# SMA-Q2_replacement_board.net
KiCad netlist of a schematic drawn in EAGLE
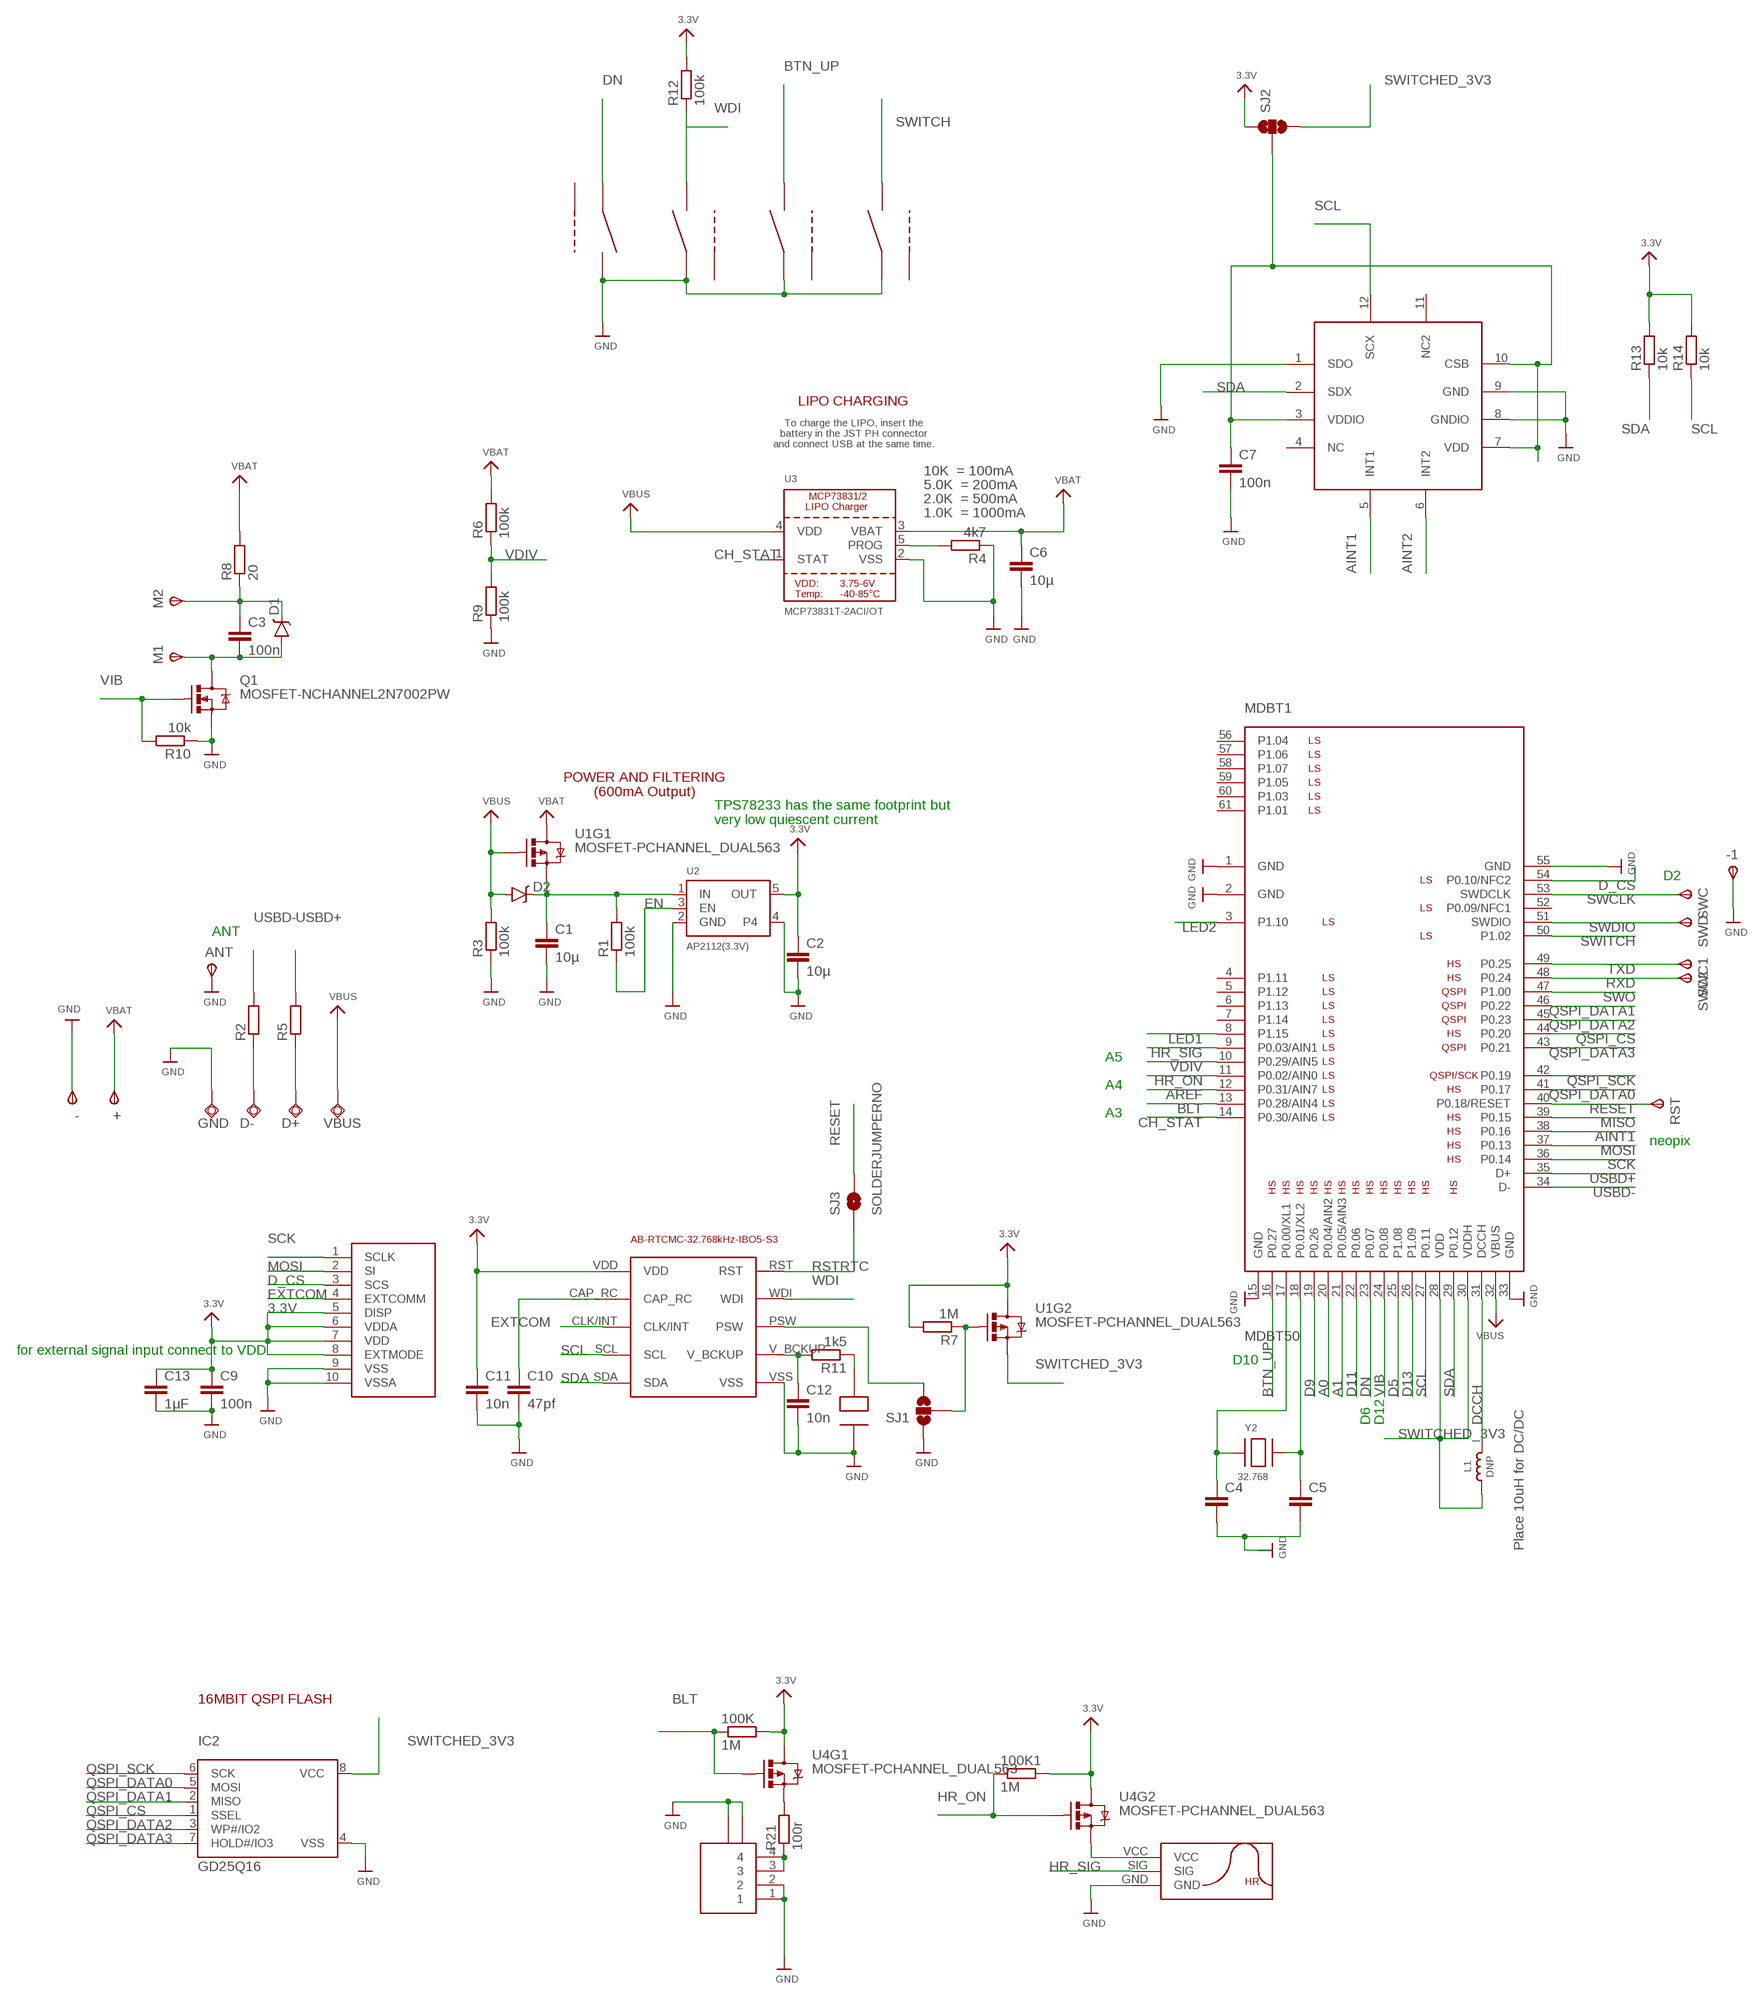
[diagram p0: schematic, sheet 1]

(export (version "E")
  (design (tool "Eeschema 10.0.6"))
  (components
    (comp (ref "+")
      (value "TPSTP09R")
      (footprint "eagle-import:TP09R")
      (libsource (lib "eagle-import") (part "TPSTP09R"))
    )
    (comp (ref "-")
      (value "TPSTP09R")
      (footprint "eagle-import:TP09R")
      (libsource (lib "eagle-import") (part "TPSTP09R"))
    )
    (comp (ref "-1")
      (value "TPSTP09R")
      (footprint "eagle-import:TP09R")
      (libsource (lib "eagle-import") (part "TPSTP09R"))
    )
    (comp (ref "100K")
      (value "1M")
      (footprint "eagle-import:R0402")
      (libsource (lib "eagle-import") (part "R-EU_R0402"))
    )
    (comp (ref "100K1")
      (value "1M")
      (footprint "eagle-import:R0402")
      (libsource (lib "eagle-import") (part "R-EU_R0402"))
    )
    (comp (ref "ANT")
      (value "TPSTP19SQ")
      (footprint "eagle-import:TP19SQ")
      (libsource (lib "eagle-import") (part "TPSTP19SQ"))
    )
    (comp (ref "C1")
      (value "10µ")
      (footprint "eagle-import:C0603")
      (libsource (lib "eagle-import") (part "C-EUC0603"))
    )
    (comp (ref "C2")
      (value "10µ")
      (footprint "eagle-import:C0603")
      (libsource (lib "eagle-import") (part "C-EUC0603"))
    )
    (comp (ref "C3")
      (value "100n")
      (footprint "eagle-import:C0402")
      (libsource (lib "eagle-import") (part "C-EUC0402"))
    )
    (comp (ref "C4")
      (value "C-EUC0402")
      (footprint "eagle-import:C0402")
      (libsource (lib "eagle-import") (part "C-EUC0402"))
    )
    (comp (ref "C5")
      (value "C-EUC0402")
      (footprint "eagle-import:C0402")
      (libsource (lib "eagle-import") (part "C-EUC0402"))
    )
    (comp (ref "C6")
      (value "10µ")
      (footprint "eagle-import:C0603")
      (libsource (lib "eagle-import") (part "C-EUC0603"))
    )
    (comp (ref "C7")
      (value "100n")
      (footprint "eagle-import:C0402")
      (libsource (lib "eagle-import") (part "C-EUC0402"))
    )
    (comp (ref "C9")
      (value "100n")
      (footprint "eagle-import:C0402")
      (libsource (lib "eagle-import") (part "C-EUC0402"))
    )
    (comp (ref "C10")
      (value "47pf")
      (footprint "eagle-import:C0402")
      (libsource (lib "eagle-import") (part "C-EUC0402"))
    )
    (comp (ref "C11")
      (value "10n")
      (footprint "eagle-import:C0402")
      (libsource (lib "eagle-import") (part "C-EUC0402"))
    )
    (comp (ref "C12")
      (value "10n")
      (footprint "eagle-import:C0402")
      (libsource (lib "eagle-import") (part "C-EUC0402"))
    )
    (comp (ref "C13")
      (value "1µF")
      (footprint "eagle-import:C0402")
      (libsource (lib "eagle-import") (part "C-EUC0402"))
    )
    (comp (ref "D+")
      (value "TPSQTP20R")
      (footprint "eagle-import:TP20R")
      (libsource (lib "eagle-import") (part "TPSQTP20R"))
    )
    (comp (ref "D-")
      (value "TPSQTP20R")
      (footprint "eagle-import:TP20R")
      (libsource (lib "eagle-import") (part "TPSQTP20R"))
    )
    (comp (ref "D1")
      (value "BAT20J")
      (footprint "eagle-import:SOD-323")
      (libsource (lib "eagle-import") (part "DIODE-SCHOTTKY-BAT20J"))
    )
    (comp (ref "D2")
      (value "BAT20J")
      (footprint "eagle-import:SOD-323")
      (libsource (lib "eagle-import") (part "DIODE-SCHOTTKY-BAT20J"))
    )
    (comp (ref "DWN")
      (value "LS12T2")
      (footprint "eagle-import:LS12T2")
      (libsource (lib "eagle-import") (part "LS12T2"))
    )
    (comp (ref "DWN1")
      (value "LS12T2")
      (footprint "eagle-import:LS12T2")
      (libsource (lib "eagle-import") (part "LS12T2"))
    )
    (comp (ref "DWN2")
      (value "LS12T2")
      (footprint "eagle-import:LS12T2")
      (libsource (lib "eagle-import") (part "LS12T2"))
    )
    (comp (ref "DWN3")
      (value "LS12T2")
      (footprint "eagle-import:LS12T2")
      (libsource (lib "eagle-import") (part "LS12T2"))
    )
    (comp (ref "GND")
      (value "TPSQTP20R")
      (footprint "eagle-import:TP20R")
      (libsource (lib "eagle-import") (part "TPSQTP20R"))
    )
    (comp (ref "IC2")
      (value "GD25Q16")
      (footprint "eagle-import:USON8")
      (libsource (lib "eagle-import") (part "SPIFLASH_8PINUX"))
    )
    (comp (ref "L1")
      (value "DNP")
      (footprint "eagle-import:_0805MP")
      (libsource (lib "eagle-import") (part "INDUCTOR_0805MP"))
    )
    (comp (ref "M1")
      (value "TPSTP09R")
      (footprint "eagle-import:TP09R")
      (libsource (lib "eagle-import") (part "TPSTP09R"))
    )
    (comp (ref "M2")
      (value "TPSTP09R")
      (footprint "eagle-import:TP09R")
      (libsource (lib "eagle-import") (part "TPSTP09R"))
    )
    (comp (ref "MDBT1")
      (value "MDBT50")
      (footprint "eagle-import:MDBT50")
      (libsource (lib "eagle-import") (part "MDBT50"))
    )
    (comp (ref "Q1")
      (value "MOSFET-NCHANNEL2N7002PW")
      (footprint "eagle-import:SOT323")
      (libsource (lib "eagle-import") (part "MOSFET-NCHANNEL2N7002PW"))
    )
    (comp (ref "R1")
      (value "100k")
      (footprint "eagle-import:R0402")
      (libsource (lib "eagle-import") (part "R-EU_R0402"))
    )
    (comp (ref "R2")
      (value "R-EU_R0402")
      (footprint "eagle-import:R0402")
      (libsource (lib "eagle-import") (part "R-EU_R0402"))
    )
    (comp (ref "R3")
      (value "100k")
      (footprint "eagle-import:R0402")
      (libsource (lib "eagle-import") (part "R-EU_R0402"))
    )
    (comp (ref "R4")
      (value "4k7")
      (footprint "eagle-import:R0402")
      (libsource (lib "eagle-import") (part "R-EU_R0402"))
    )
    (comp (ref "R5")
      (value "R-EU_R0402")
      (footprint "eagle-import:R0402")
      (libsource (lib "eagle-import") (part "R-EU_R0402"))
    )
    (comp (ref "R6")
      (value "100k")
      (footprint "eagle-import:R0402")
      (libsource (lib "eagle-import") (part "R-EU_R0402"))
    )
    (comp (ref "R7")
      (value "1M")
      (footprint "eagle-import:R0402")
      (libsource (lib "eagle-import") (part "R-EU_R0402"))
    )
    (comp (ref "R8")
      (value "20")
      (footprint "eagle-import:R0402")
      (libsource (lib "eagle-import") (part "R-EU_R0402"))
    )
    (comp (ref "R9")
      (value "100k")
      (footprint "eagle-import:R0402")
      (libsource (lib "eagle-import") (part "R-EU_R0402"))
    )
    (comp (ref "R10")
      (value "10k")
      (footprint "eagle-import:R0402")
      (libsource (lib "eagle-import") (part "R-EU_R0402"))
    )
    (comp (ref "R11")
      (value "1k5")
      (footprint "eagle-import:R0402")
      (libsource (lib "eagle-import") (part "R-EU_R0402"))
    )
    (comp (ref "R12")
      (value "100k")
      (footprint "eagle-import:R0402")
      (libsource (lib "eagle-import") (part "R-EU_R0402"))
    )
    (comp (ref "R13")
      (value "10k")
      (footprint "eagle-import:R0402")
      (libsource (lib "eagle-import") (part "R-EU_R0402"))
    )
    (comp (ref "R14")
      (value "10k")
      (footprint "eagle-import:R0402")
      (libsource (lib "eagle-import") (part "R-EU_R0402"))
    )
    (comp (ref "R21")
      (value "100r")
      (footprint "eagle-import:R0402")
      (libsource (lib "eagle-import") (part "R-EU_R0402"))
    )
    (comp (ref "RST")
      (value "TPSTP09R")
      (footprint "eagle-import:TP09R")
      (libsource (lib "eagle-import") (part "TPSTP09R"))
    )
    (comp (ref "SJ1")
      (value "SOLDERJUMPER_2WAYS")
      (footprint "eagle-import:SJ_3")
      (libsource (lib "eagle-import") (part "SOLDERJUMPER_2WAYS"))
    )
    (comp (ref "SJ2")
      (value "SOLDERJUMPER_2WAYS")
      (footprint "eagle-import:SJ_3")
      (libsource (lib "eagle-import") (part "SOLDERJUMPER_2WAYS"))
    )
    (comp (ref "SJ3")
      (value "SOLDERJUMPERNO")
      (footprint "eagle-import:SJ_2S-NO")
      (libsource (lib "eagle-import") (part "SOLDERJUMPERNO"))
    )
    (comp (ref "SWC")
      (value "TPSTP09R")
      (footprint "eagle-import:TP09R")
      (libsource (lib "eagle-import") (part "TPSTP09R"))
    )
    (comp (ref "SWC1")
      (value "TPSTP09R")
      (footprint "eagle-import:TP09R")
      (libsource (lib "eagle-import") (part "TPSTP09R"))
    )
    (comp (ref "SWC2")
      (value "TPSTP09R")
      (footprint "eagle-import:TP09R")
      (libsource (lib "eagle-import") (part "TPSTP09R"))
    )
    (comp (ref "SWD")
      (value "TPSTP09R")
      (footprint "eagle-import:TP09R")
      (libsource (lib "eagle-import") (part "TPSTP09R"))
    )
    (comp (ref "U$1")
      (value "AB-RTCMC-32.768KHZ-IBO5-S3")
      (footprint "eagle-import:AB-RTCMC-32.768KHZ-IBO5-S3")
      (libsource (lib "eagle-import") (part "AB-RTCMC-32.768KHZ-IBO5-S3"))
    )
    (comp (ref "U$2")
      (value "SHARP_MEM_DISP")
      (footprint "eagle-import:Y5BW")
      (libsource (lib "eagle-import") (part "SHARP_MEM_DISP"))
    )
    (comp (ref "U$6")
      (value "Y5B-4PIN")
      (footprint "eagle-import:Y5B-4PIN")
      (libsource (lib "eagle-import") (part "Y5B-4PIN"))
    )
    (comp (ref "U$7")
      (value "BMA400")
      (footprint "eagle-import:BMA400")
      (libsource (lib "eagle-import") (part "BMA400"))
    )
    (comp (ref "U$15")
      (value "CPH3225A")
      (footprint "eagle-import:CPH3225A")
      (libsource (lib "eagle-import") (part "CPH3225A"))
    )
    (comp (ref "U$45")
      (value "HR_PADS")
      (footprint "eagle-import:HR_PADS")
      (libsource (lib "eagle-import") (part "HR_PADS"))
    )
    (comp (ref "U1")
      (value "MOSFET-PCHANNEL_DUAL563")
      (footprint "eagle-import:SOT563")
      (libsource (lib "eagle-import") (part "MOSFET-PCHANNEL_DUAL563"))
    )
    (comp (ref "U2")
      (value "AP2112(3.3V)")
      (footprint "eagle-import:SOT23-5")
      (libsource (lib "eagle-import") (part "VREG_SOT23-5"))
    )
    (comp (ref "U3")
      (value "MCP73831T-2ACI/OT")
      (footprint "eagle-import:SOT23-5")
      (libsource (lib "eagle-import") (part "MCP73831/2"))
    )
    (comp (ref "U4")
      (value "MOSFET-PCHANNEL_DUAL563")
      (footprint "eagle-import:SOT563")
      (libsource (lib "eagle-import") (part "MOSFET-PCHANNEL_DUAL563"))
    )
    (comp (ref "VBUS")
      (value "TPSQTP20R")
      (footprint "eagle-import:TP20R")
      (libsource (lib "eagle-import") (part "TPSQTP20R"))
    )
    (comp (ref "Y2")
      (value "32.768")
      (footprint "eagle-import:XTAL3215")
      (libsource (lib "eagle-import") (part "XTAL-3.2X1.5"))
    )
  )
  (nets
    (net (code "1") (name "/A0") (class "Default")
      (node (ref "MDBT1") (pin "20") (pinfunction "P0.04/AIN2_20") (pintype "bidirectional"))
    )
    (net (code "2") (name "/A1") (class "Default")
      (node (ref "MDBT1") (pin "21") (pinfunction "P0.05/AIN3_21") (pintype "bidirectional"))
    )
    (net (code "3") (name "/AINT1") (class "Default")
      (node (ref "MDBT1") (pin "38") (pinfunction "P0.16_38") (pintype "bidirectional"))
      (node (ref "U$7") (pin "5") (pinfunction "INT1_5") (pintype "bidirectional"))
    )
    (net (code "4") (name "/AINT2") (class "Default")
      (node (ref "U$7") (pin "6") (pinfunction "INT2_6") (pintype "bidirectional"))
    )
    (net (code "5") (name "/AREF") (class "Default")
      (node (ref "MDBT1") (pin "12") (pinfunction "P0.31/AIN7_12") (pintype "bidirectional"))
    )
    (net (code "6") (name "/BLT") (class "Default")
      (node (ref "100K") (pin "1") (pinfunction "1_1") (pintype "passive"))
      (node (ref "MDBT1") (pin "13") (pinfunction "P0.28/AIN4_13") (pintype "bidirectional"))
      (node (ref "U4") (pin "G1") (pinfunction "G_G1") (pintype "passive"))
    )
    (net (code "7") (name "/BTN_UP") (class "Default")
      (node (ref "DWN2") (pin "1") (pinfunction "1_1") (pintype "bidirectional"))
      (node (ref "MDBT1") (pin "16") (pinfunction "P0.27_16") (pintype "bidirectional"))
    )
    (net (code "8") (name "/CH_STAT") (class "Default")
      (node (ref "MDBT1") (pin "14") (pinfunction "P0.30/AIN6_14") (pintype "bidirectional"))
      (node (ref "U3") (pin "1") (pinfunction "STAT_1") (pintype "output"))
    )
    (net (code "9") (name "/D5") (class "Default")
      (node (ref "MDBT1") (pin "25") (pinfunction "P1.08_25") (pintype "bidirectional"))
    )
    (net (code "10") (name "/D9") (class "Default")
      (node (ref "MDBT1") (pin "19") (pinfunction "P0.26_19") (pintype "bidirectional"))
    )
    (net (code "11") (name "/D11") (class "Default")
      (node (ref "MDBT1") (pin "22") (pinfunction "P0.06_22") (pintype "bidirectional"))
    )
    (net (code "12") (name "/D13") (class "Default")
      (node (ref "MDBT1") (pin "26") (pinfunction "P1.09_26") (pintype "bidirectional"))
    )
    (net (code "13") (name "/DCCH") (class "Default")
      (node (ref "L1") (pin "2") (pinfunction "2_2") (pintype "passive"))
      (node (ref "MDBT1") (pin "31") (pinfunction "DCCH_31") (pintype "bidirectional"))
    )
    (net (code "14") (name "/DN") (class "Default")
      (node (ref "DWN") (pin "2") (pinfunction "2_2") (pintype "bidirectional"))
      (node (ref "MDBT1") (pin "23") (pinfunction "P0.07_23") (pintype "bidirectional"))
    )
    (net (code "15") (name "/D_CS") (class "Default")
      (node (ref "MDBT1") (pin "54") (pinfunction "P0.10/NFC2_54") (pintype "bidirectional"))
      (node (ref "U$2") (pin "3") (pinfunction "SCS_3") (pintype "bidirectional"))
    )
    (net (code "16") (name "/EN") (class "Default")
      (node (ref "R1") (pin "1") (pinfunction "1_1") (pintype "passive"))
      (node (ref "U2") (pin "3") (pinfunction "EN_3") (pintype "input"))
    )
    (net (code "17") (name "/EXTCOM") (class "Default")
      (node (ref "U$1") (pin "CLK/INT") (pinfunction "CLK/INT_CLK/INT") (pintype "bidirectional"))
      (node (ref "U$2") (pin "4") (pinfunction "EXTCOMM_4") (pintype "bidirectional"))
    )
    (net (code "18") (name "/HR_ON") (class "Default")
      (node (ref "100K1") (pin "1") (pinfunction "1_1") (pintype "passive"))
      (node (ref "MDBT1") (pin "11") (pinfunction "P0.02/AIN0_11") (pintype "bidirectional"))
      (node (ref "U4") (pin "G2") (pinfunction "G_G2") (pintype "passive"))
    )
    (net (code "19") (name "/HR_SIG") (class "Default")
      (node (ref "MDBT1") (pin "9") (pinfunction "P0.03/AIN1_9") (pintype "bidirectional"))
      (node (ref "U$45") (pin "SIG") (pinfunction "SIG_SIG") (pintype "bidirectional"))
    )
    (net (code "20") (name "/LED1") (class "Default")
      (node (ref "MDBT1") (pin "8") (pinfunction "P1.15_8") (pintype "bidirectional"))
    )
    (net (code "21") (name "/LED2") (class "Default")
      (node (ref "MDBT1") (pin "3") (pinfunction "P1.10_3") (pintype "bidirectional"))
    )
    (net (code "22") (name "/MISO") (class "Default")
      (node (ref "MDBT1") (pin "39") (pinfunction "P0.15_39") (pintype "bidirectional"))
    )
    (net (code "23") (name "/MOSI") (class "Default")
      (node (ref "MDBT1") (pin "37") (pinfunction "P0.13_37") (pintype "bidirectional"))
      (node (ref "U$2") (pin "2") (pinfunction "SI_2") (pintype "bidirectional"))
    )
    (net (code "24") (name "/QSPI_CS") (class "Default")
      (node (ref "IC2") (pin "1") (pinfunction "SSEL_1") (pintype "bidirectional"))
      (node (ref "MDBT1") (pin "44") (pinfunction "P0.20_44") (pintype "bidirectional"))
    )
    (net (code "25") (name "/QSPI_DATA0") (class "Default")
      (node (ref "IC2") (pin "5") (pinfunction "MOSI_5") (pintype "bidirectional"))
      (node (ref "MDBT1") (pin "41") (pinfunction "P0.17_41") (pintype "bidirectional"))
    )
    (net (code "26") (name "/QSPI_DATA1") (class "Default")
      (node (ref "IC2") (pin "2") (pinfunction "MISO_2") (pintype "bidirectional"))
      (node (ref "MDBT1") (pin "46") (pinfunction "P0.22_46") (pintype "bidirectional"))
    )
    (net (code "27") (name "/QSPI_DATA2") (class "Default")
      (node (ref "IC2") (pin "3") (pinfunction "WP#/IO2_3") (pintype "bidirectional"))
      (node (ref "MDBT1") (pin "45") (pinfunction "P0.23_45") (pintype "bidirectional"))
    )
    (net (code "28") (name "/QSPI_DATA3") (class "Default")
      (node (ref "IC2") (pin "7") (pinfunction "HOLD#/IO3_7") (pintype "bidirectional"))
      (node (ref "MDBT1") (pin "43") (pinfunction "P0.21_43") (pintype "bidirectional"))
    )
    (net (code "29") (name "/QSPI_SCK") (class "Default")
      (node (ref "IC2") (pin "6") (pinfunction "SCK_6") (pintype "bidirectional"))
      (node (ref "MDBT1") (pin "42") (pinfunction "P0.19_42") (pintype "bidirectional"))
    )
    (net (code "30") (name "/RESET") (class "Default")
      (node (ref "MDBT1") (pin "40") (pinfunction "P0.18/RESET_40") (pintype "bidirectional"))
      (node (ref "RST") (pin "TP") (pinfunction "PP_TP") (pintype "input"))
      (node (ref "SJ3") (pin "2") (pinfunction "2_2") (pintype "passive"))
    )
    (net (code "31") (name "/RSTRTC") (class "Default")
      (node (ref "SJ3") (pin "1") (pinfunction "1_1") (pintype "passive"))
      (node (ref "U$1") (pin "RST") (pinfunction "RST_RST") (pintype "bidirectional"))
    )
    (net (code "32") (name "/RXD") (class "Default")
      (node (ref "MDBT1") (pin "48") (pinfunction "P0.24_48") (pintype "bidirectional"))
      (node (ref "SWC2") (pin "TP") (pinfunction "PP_TP") (pintype "input"))
    )
    (net (code "33") (name "/SCK") (class "Default")
      (node (ref "MDBT1") (pin "36") (pinfunction "P0.14_36") (pintype "bidirectional"))
      (node (ref "U$2") (pin "1") (pinfunction "SCLK_1") (pintype "bidirectional"))
    )
    (net (code "34") (name "/SCL") (class "Default")
      (node (ref "MDBT1") (pin "27") (pinfunction "P0.11_27") (pintype "bidirectional"))
      (node (ref "R14") (pin "1") (pinfunction "1_1") (pintype "passive"))
      (node (ref "U$1") (pin "SCL") (pinfunction "SCL_SCL") (pintype "bidirectional"))
      (node (ref "U$7") (pin "12") (pinfunction "SCX_12") (pintype "bidirectional"))
    )
    (net (code "35") (name "/SDA") (class "Default")
      (node (ref "MDBT1") (pin "29") (pinfunction "P0.12_29") (pintype "bidirectional"))
      (node (ref "R13") (pin "1") (pinfunction "1_1") (pintype "passive"))
      (node (ref "U$1") (pin "SDA") (pinfunction "SDA_SDA") (pintype "bidirectional"))
      (node (ref "U$7") (pin "2") (pinfunction "SDX_2") (pintype "bidirectional"))
    )
    (net (code "36") (name "/SWCLK") (class "Default")
      (node (ref "MDBT1") (pin "53") (pinfunction "SWDCLK_53") (pintype "bidirectional"))
      (node (ref "SWC") (pin "TP") (pinfunction "PP_TP") (pintype "input"))
    )
    (net (code "37") (name "/SWDIO") (class "Default")
      (node (ref "MDBT1") (pin "51") (pinfunction "SWDIO_51") (pintype "bidirectional"))
      (node (ref "SWD") (pin "TP") (pinfunction "PP_TP") (pintype "input"))
    )
    (net (code "38") (name "/SWITCH") (class "Default")
      (node (ref "DWN3") (pin "1") (pinfunction "1_1") (pintype "bidirectional"))
      (node (ref "MDBT1") (pin "50") (pinfunction "P1.02_50") (pintype "bidirectional"))
    )
    (net (code "39") (name "/SWITCHED_3V3") (class "Default")
      (node (ref "IC2") (pin "8") (pinfunction "VCC_8") (pintype "bidirectional"))
      (node (ref "L1") (pin "1") (pinfunction "1_1") (pintype "passive"))
      (node (ref "MDBT1") (pin "28") (pinfunction "VDD_28") (pintype "bidirectional"))
      (node (ref "MDBT1") (pin "30") (pinfunction "VDDH_30") (pintype "bidirectional"))
      (node (ref "SJ2") (pin "3") (pinfunction "3_3") (pintype "passive"))
      (node (ref "U1") (pin "S2") (pinfunction "S_S2") (pintype "passive"))
    )
    (net (code "40") (name "/SWO") (class "Default")
      (node (ref "MDBT1") (pin "47") (pinfunction "P1.00_47") (pintype "bidirectional"))
    )
    (net (code "41") (name "/TXD") (class "Default")
      (node (ref "MDBT1") (pin "49") (pinfunction "P0.25_49") (pintype "bidirectional"))
      (node (ref "SWC1") (pin "TP") (pinfunction "PP_TP") (pintype "input"))
    )
    (net (code "42") (name "/USBD+") (class "Default")
      (node (ref "MDBT1") (pin "35") (pinfunction "D+_35") (pintype "bidirectional"))
      (node (ref "R5") (pin "2") (pinfunction "2_2") (pintype "passive"))
    )
    (net (code "43") (name "/USBD-") (class "Default")
      (node (ref "MDBT1") (pin "34") (pinfunction "D-_34") (pintype "bidirectional"))
      (node (ref "R2") (pin "2") (pinfunction "2_2") (pintype "passive"))
    )
    (net (code "44") (name "/VDIV") (class "Default")
      (node (ref "MDBT1") (pin "10") (pinfunction "P0.29/AIN5_10") (pintype "bidirectional"))
      (node (ref "R6") (pin "1") (pinfunction "1_1") (pintype "passive"))
      (node (ref "R9") (pin "2") (pinfunction "2_2") (pintype "passive"))
    )
    (net (code "45") (name "/VIB") (class "Default")
      (node (ref "MDBT1") (pin "24") (pinfunction "P0.08_24") (pintype "bidirectional"))
      (node (ref "Q1") (pin "1") (pinfunction "G_1") (pintype "passive"))
      (node (ref "R10") (pin "2") (pinfunction "2_2") (pintype "passive"))
    )
    (net (code "46") (name "/WDI") (class "Default")
      (node (ref "DWN1") (pin "1") (pinfunction "1_1") (pintype "bidirectional"))
      (node (ref "R12") (pin "1") (pinfunction "1_1") (pintype "passive"))
      (node (ref "U$1") (pin "WDI") (pinfunction "WDI_WDI") (pintype "bidirectional"))
    )
    (net (code "47") (name "3.3V") (class "Default")
      (node (ref "100K") (pin "2") (pinfunction "2_2") (pintype "passive"))
      (node (ref "100K1") (pin "2") (pinfunction "2_2") (pintype "passive"))
      (node (ref "C11") (pin "1") (pinfunction "1_1") (pintype "passive"))
      (node (ref "C13") (pin "1") (pinfunction "1_1") (pintype "passive"))
      (node (ref "C2") (pin "1") (pinfunction "1_1") (pintype "passive"))
      (node (ref "C9") (pin "1") (pinfunction "1_1") (pintype "passive"))
      (node (ref "R12") (pin "2") (pinfunction "2_2") (pintype "passive"))
      (node (ref "R13") (pin "2") (pinfunction "2_2") (pintype "passive"))
      (node (ref "R14") (pin "2") (pinfunction "2_2") (pintype "passive"))
      (node (ref "R7") (pin "2") (pinfunction "2_2") (pintype "passive"))
      (node (ref "SJ2") (pin "1") (pinfunction "1_1") (pintype "passive"))
      (node (ref "U$1") (pin "VDD") (pinfunction "VDD_VDD") (pintype "bidirectional"))
      (node (ref "U$2") (pin "5") (pinfunction "DISP_5") (pintype "bidirectional"))
      (node (ref "U$2") (pin "6") (pinfunction "VDDA_6") (pintype "bidirectional"))
      (node (ref "U$2") (pin "7") (pinfunction "VDD_7") (pintype "bidirectional"))
      (node (ref "U$2") (pin "8") (pinfunction "EXTMODE_8") (pintype "bidirectional"))
      (node (ref "U1") (pin "D2") (pinfunction "D_D2") (pintype "passive"))
      (node (ref "U2") (pin "5") (pinfunction "OUT_5") (pintype "power_in"))
      (node (ref "U4") (pin "D1") (pinfunction "D_D1") (pintype "passive"))
      (node (ref "U4") (pin "D2") (pinfunction "D_D2") (pintype "passive"))
    )
    (net (code "48") (name "GND") (class "Default")
      (node (ref "-") (pin "TP") (pinfunction "PP_TP") (pintype "input"))
      (node (ref "-1") (pin "TP") (pinfunction "PP_TP") (pintype "input"))
      (node (ref "ANT") (pin "TP") (pinfunction "PP_TP") (pintype "input"))
      (node (ref "C1") (pin "2") (pinfunction "2_2") (pintype "passive"))
      (node (ref "C10") (pin "2") (pinfunction "2_2") (pintype "passive"))
      (node (ref "C11") (pin "2") (pinfunction "2_2") (pintype "passive"))
      (node (ref "C12") (pin "2") (pinfunction "2_2") (pintype "passive"))
      (node (ref "C13") (pin "2") (pinfunction "2_2") (pintype "passive"))
      (node (ref "C2") (pin "2") (pinfunction "2_2") (pintype "passive"))
      (node (ref "C4") (pin "2") (pinfunction "2_2") (pintype "passive"))
      (node (ref "C5") (pin "2") (pinfunction "2_2") (pintype "passive"))
      (node (ref "C6") (pin "2") (pinfunction "2_2") (pintype "passive"))
      (node (ref "C7") (pin "2") (pinfunction "2_2") (pintype "passive"))
      (node (ref "C9") (pin "2") (pinfunction "2_2") (pintype "passive"))
      (node (ref "DWN") (pin "1") (pinfunction "1_1") (pintype "bidirectional"))
      (node (ref "DWN1") (pin "2") (pinfunction "2_2") (pintype "bidirectional"))
      (node (ref "DWN2") (pin "2") (pinfunction "2_2") (pintype "bidirectional"))
      (node (ref "DWN3") (pin "2") (pinfunction "2_2") (pintype "bidirectional"))
      (node (ref "GND") (pin "TP") (pinfunction "TP_TP") (pintype "input"))
      (node (ref "IC2") (pin "4") (pinfunction "VSS_4") (pintype "bidirectional"))
      (node (ref "MDBT1") (pin "1") (pinfunction "GND_1") (pintype "bidirectional"))
      (node (ref "MDBT1") (pin "15") (pinfunction "GND_15") (pintype "bidirectional"))
      (node (ref "MDBT1") (pin "2") (pinfunction "GND_2") (pintype "bidirectional"))
      (node (ref "MDBT1") (pin "33") (pinfunction "GND_33") (pintype "bidirectional"))
      (node (ref "MDBT1") (pin "55") (pinfunction "GND_55") (pintype "bidirectional"))
      (node (ref "Q1") (pin "2") (pinfunction "S_2") (pintype "passive"))
      (node (ref "R10") (pin "1") (pinfunction "1_1") (pintype "passive"))
      (node (ref "R3") (pin "1") (pinfunction "1_1") (pintype "passive"))
      (node (ref "R4") (pin "1") (pinfunction "1_1") (pintype "passive"))
      (node (ref "R9") (pin "1") (pinfunction "1_1") (pintype "passive"))
      (node (ref "SJ1") (pin "1") (pinfunction "1_1") (pintype "passive"))
      (node (ref "U$1") (pin "VSS") (pinfunction "VSS_VSS") (pintype "bidirectional"))
      (node (ref "U$15") (pin "-") (pinfunction "-_-") (pintype "bidirectional"))
      (node (ref "U$2") (pin "10") (pinfunction "VSSA_10") (pintype "bidirectional"))
      (node (ref "U$2") (pin "9") (pinfunction "VSS_9") (pintype "bidirectional"))
      (node (ref "U$45") (pin "GND") (pinfunction "GND_GND") (pintype "bidirectional"))
      (node (ref "U$6") (pin "1") (pinfunction "1_1") (pintype "bidirectional"))
      (node (ref "U$6") (pin "2") (pinfunction "2_2") (pintype "bidirectional"))
      (node (ref "U$6") (pin "H1") (pinfunction "P$5_H1") (pintype "bidirectional"))
      (node (ref "U$6") (pin "H2") (pinfunction "P$6_H2") (pintype "bidirectional"))
      (node (ref "U$7") (pin "1") (pinfunction "SDO_1") (pintype "bidirectional"))
      (node (ref "U$7") (pin "8") (pinfunction "GNDIO_8") (pintype "bidirectional"))
      (node (ref "U$7") (pin "9") (pinfunction "GND_9") (pintype "bidirectional"))
      (node (ref "U2") (pin "2") (pinfunction "GND_2") (pintype "power_in"))
      (node (ref "U2") (pin "4") (pinfunction "P4_4") (pintype "bidirectional"))
      (node (ref "U3") (pin "2") (pinfunction "VSS_2") (pintype "power_in"))
    )
    (net (code "49") (name "Net-(C10-Pad1)") (class "Default")
      (node (ref "C10") (pin "1") (pinfunction "1_1") (pintype "passive"))
      (node (ref "U$1") (pin "CAP_RC") (pinfunction "CAP_RC_CAP_RC") (pintype "bidirectional"))
    )
    (net (code "50") (name "Net-(C12-Pad1)") (class "Default")
      (node (ref "C12") (pin "1") (pinfunction "1_1") (pintype "passive"))
      (node (ref "R11") (pin "2") (pinfunction "2_2") (pintype "passive"))
      (node (ref "U$1") (pin "V_BCKUP") (pinfunction "V_BCKUP_V_BCKUP") (pintype "bidirectional"))
    )
    (net (code "51") (name "Net-(D+-PadTP)") (class "Default")
      (node (ref "D+") (pin "TP") (pinfunction "TP_TP") (pintype "input"))
      (node (ref "R5") (pin "1") (pinfunction "1_1") (pintype "passive"))
    )
    (net (code "52") (name "Net-(D--PadTP)") (class "Default")
      (node (ref "D-") (pin "TP") (pinfunction "TP_TP") (pintype "input"))
      (node (ref "R2") (pin "1") (pinfunction "1_1") (pintype "passive"))
    )
    (net (code "53") (name "Net-(M1-PP)") (class "Default")
      (node (ref "C3") (pin "2") (pinfunction "2_2") (pintype "passive"))
      (node (ref "D1") (pin "A") (pinfunction "A_A") (pintype "passive"))
      (node (ref "M1") (pin "TP") (pinfunction "PP_TP") (pintype "input"))
      (node (ref "Q1") (pin "3") (pinfunction "D_3") (pintype "passive"))
    )
    (net (code "54") (name "Net-(M2-PP)") (class "Default")
      (node (ref "C3") (pin "1") (pinfunction "1_1") (pintype "passive"))
      (node (ref "D1") (pin "C") (pinfunction "C_C") (pintype "passive"))
      (node (ref "M2") (pin "TP") (pinfunction "PP_TP") (pintype "input"))
      (node (ref "R8") (pin "1") (pinfunction "1_1") (pintype "passive"))
    )
    (net (code "55") (name "Net-(MDBT1-P0.00{slash}XL1)") (class "Default")
      (node (ref "C4") (pin "1") (pinfunction "1_1") (pintype "passive"))
      (node (ref "MDBT1") (pin "17") (pinfunction "P0.00/XL1_17") (pintype "bidirectional"))
      (node (ref "Y2") (pin "P$1") (pinfunction "P$1_P$1") (pintype "bidirectional"))
    )
    (net (code "56") (name "Net-(MDBT1-P0.01{slash}XL2)") (class "Default")
      (node (ref "C5") (pin "1") (pinfunction "1_1") (pintype "passive"))
      (node (ref "MDBT1") (pin "18") (pinfunction "P0.01/XL2_18") (pintype "bidirectional"))
      (node (ref "Y2") (pin "P$2") (pinfunction "P$2_P$2") (pintype "bidirectional"))
    )
    (net (code "57") (name "Net-(R11-Pad1)") (class "Default")
      (node (ref "R11") (pin "1") (pinfunction "1_1") (pintype "passive"))
      (node (ref "U$15") (pin "+") (pinfunction "+_+") (pintype "bidirectional"))
    )
    (net (code "58") (name "Net-(R21-Pad1)") (class "Default")
      (node (ref "R21") (pin "1") (pinfunction "1_1") (pintype "passive"))
      (node (ref "U$6") (pin "3") (pinfunction "3_3") (pintype "bidirectional"))
      (node (ref "U$6") (pin "4") (pinfunction "4_4") (pintype "bidirectional"))
    )
    (net (code "59") (name "Net-(SJ1-Pad3)") (class "Default")
      (node (ref "SJ1") (pin "3") (pinfunction "3_3") (pintype "passive"))
      (node (ref "U$1") (pin "PSW") (pinfunction "PSW_PSW") (pintype "bidirectional"))
    )
    (net (code "60") (name "Net-(U$7-CSB)") (class "Default")
      (node (ref "C7") (pin "1") (pinfunction "1_1") (pintype "passive"))
      (node (ref "SJ2") (pin "2") (pinfunction "2_2") (pintype "passive"))
      (node (ref "U$7") (pin "10") (pinfunction "CSB_10") (pintype "bidirectional"))
      (node (ref "U$7") (pin "3") (pinfunction "VDDIO_3") (pintype "bidirectional"))
      (node (ref "U$7") (pin "7") (pinfunction "VDD_7") (pintype "bidirectional"))
    )
    (net (code "61") (name "Net-(U1A-S)") (class "Default")
      (node (ref "C1") (pin "1") (pinfunction "1_1") (pintype "passive"))
      (node (ref "D2") (pin "C") (pinfunction "C_C") (pintype "passive"))
      (node (ref "R1") (pin "2") (pinfunction "2_2") (pintype "passive"))
      (node (ref "U1") (pin "S1") (pinfunction "S_S1") (pintype "passive"))
      (node (ref "U2") (pin "1") (pinfunction "IN_1") (pintype "power_in"))
    )
    (net (code "62") (name "Net-(U1B-G)") (class "Default")
      (node (ref "R7") (pin "1") (pinfunction "1_1") (pintype "passive"))
      (node (ref "SJ1") (pin "2") (pinfunction "2_2") (pintype "passive"))
      (node (ref "U1") (pin "G2") (pinfunction "G_G2") (pintype "passive"))
    )
    (net (code "63") (name "Net-(U3-PROG)") (class "Default")
      (node (ref "R4") (pin "2") (pinfunction "2_2") (pintype "passive"))
      (node (ref "U3") (pin "5") (pinfunction "PROG_5") (pintype "input"))
    )
    (net (code "64") (name "Net-(U4A-S)") (class "Default")
      (node (ref "R21") (pin "2") (pinfunction "2_2") (pintype "passive"))
      (node (ref "U4") (pin "S1") (pinfunction "S_S1") (pintype "passive"))
    )
    (net (code "65") (name "Net-(U4B-S)") (class "Default")
      (node (ref "U$45") (pin "VCC") (pinfunction "VCC_VCC") (pintype "bidirectional"))
      (node (ref "U4") (pin "S2") (pinfunction "S_S2") (pintype "passive"))
    )
    (net (code "66") (name "VBAT") (class "Default")
      (node (ref "+") (pin "TP") (pinfunction "PP_TP") (pintype "input"))
      (node (ref "C6") (pin "1") (pinfunction "1_1") (pintype "passive"))
      (node (ref "R6") (pin "2") (pinfunction "2_2") (pintype "passive"))
      (node (ref "R8") (pin "2") (pinfunction "2_2") (pintype "passive"))
      (node (ref "U1") (pin "D1") (pinfunction "D_D1") (pintype "passive"))
      (node (ref "U3") (pin "3") (pinfunction "VBAT_3") (pintype "power_in"))
    )
    (net (code "67") (name "VBUS") (class "Default")
      (node (ref "D2") (pin "A") (pinfunction "A_A") (pintype "passive"))
      (node (ref "MDBT1") (pin "32") (pinfunction "VBUS_32") (pintype "bidirectional"))
      (node (ref "R3") (pin "2") (pinfunction "2_2") (pintype "passive"))
      (node (ref "U1") (pin "G1") (pinfunction "G_G1") (pintype "passive"))
      (node (ref "U3") (pin "4") (pinfunction "VDD_4") (pintype "power_in"))
      (node (ref "VBUS") (pin "TP") (pinfunction "TP_TP") (pintype "input"))
    )
    (net (code "68") (name "unconnected-(DWN-FRM-PadFRAME)") (class "Default")
      (node (ref "DWN") (pin "FRAME") (pinfunction "FRM_FRAME") (pintype "bidirectional"))
    )
    (net (code "69") (name "unconnected-(DWN1-FRM-PadFRAME)") (class "Default")
      (node (ref "DWN1") (pin "FRAME") (pinfunction "FRM_FRAME") (pintype "bidirectional"))
    )
    (net (code "70") (name "unconnected-(DWN2-FRM-PadFRAME)") (class "Default")
      (node (ref "DWN2") (pin "FRAME") (pinfunction "FRM_FRAME") (pintype "bidirectional"))
    )
    (net (code "71") (name "unconnected-(DWN3-FRM-PadFRAME)") (class "Default")
      (node (ref "DWN3") (pin "FRAME") (pinfunction "FRM_FRAME") (pintype "bidirectional"))
    )
    (net (code "72") (name "unconnected-(MDBT1-P0.09{slash}NFC1-Pad52)") (class "Default")
      (node (ref "MDBT1") (pin "52") (pinfunction "P0.09/NFC1_52") (pintype "bidirectional"))
    )
    (net (code "73") (name "unconnected-(MDBT1-P1.01-Pad61)") (class "Default")
      (node (ref "MDBT1") (pin "61") (pinfunction "P1.01_61") (pintype "bidirectional"))
    )
    (net (code "74") (name "unconnected-(MDBT1-P1.03-Pad60)") (class "Default")
      (node (ref "MDBT1") (pin "60") (pinfunction "P1.03_60") (pintype "bidirectional"))
    )
    (net (code "75") (name "unconnected-(MDBT1-P1.04-Pad56)") (class "Default")
      (node (ref "MDBT1") (pin "56") (pinfunction "P1.04_56") (pintype "bidirectional"))
    )
    (net (code "76") (name "unconnected-(MDBT1-P1.05-Pad59)") (class "Default")
      (node (ref "MDBT1") (pin "59") (pinfunction "P1.05_59") (pintype "bidirectional"))
    )
    (net (code "77") (name "unconnected-(MDBT1-P1.06-Pad57)") (class "Default")
      (node (ref "MDBT1") (pin "57") (pinfunction "P1.06_57") (pintype "bidirectional"))
    )
    (net (code "78") (name "unconnected-(MDBT1-P1.07-Pad58)") (class "Default")
      (node (ref "MDBT1") (pin "58") (pinfunction "P1.07_58") (pintype "bidirectional"))
    )
    (net (code "79") (name "unconnected-(MDBT1-P1.11-Pad4)") (class "Default")
      (node (ref "MDBT1") (pin "4") (pinfunction "P1.11_4") (pintype "bidirectional"))
    )
    (net (code "80") (name "unconnected-(MDBT1-P1.12-Pad5)") (class "Default")
      (node (ref "MDBT1") (pin "5") (pinfunction "P1.12_5") (pintype "bidirectional"))
    )
    (net (code "81") (name "unconnected-(MDBT1-P1.13-Pad6)") (class "Default")
      (node (ref "MDBT1") (pin "6") (pinfunction "P1.13_6") (pintype "bidirectional"))
    )
    (net (code "82") (name "unconnected-(MDBT1-P1.14-Pad7)") (class "Default")
      (node (ref "MDBT1") (pin "7") (pinfunction "P1.14_7") (pintype "bidirectional"))
    )
    (net (code "83") (name "unconnected-(U$7-NC-Pad4)") (class "Default")
      (node (ref "U$7") (pin "4") (pinfunction "NC_4") (pintype "bidirectional"))
    )
    (net (code "84") (name "unconnected-(U$7-NC2-Pad11)") (class "Default")
      (node (ref "U$7") (pin "11") (pinfunction "NC2_11") (pintype "bidirectional"))
    )
  )
)
